# half-pint-turbidimeter_tsl230rd_2_0_1.net
KiCad netlist of a schematic drawn in EAGLE
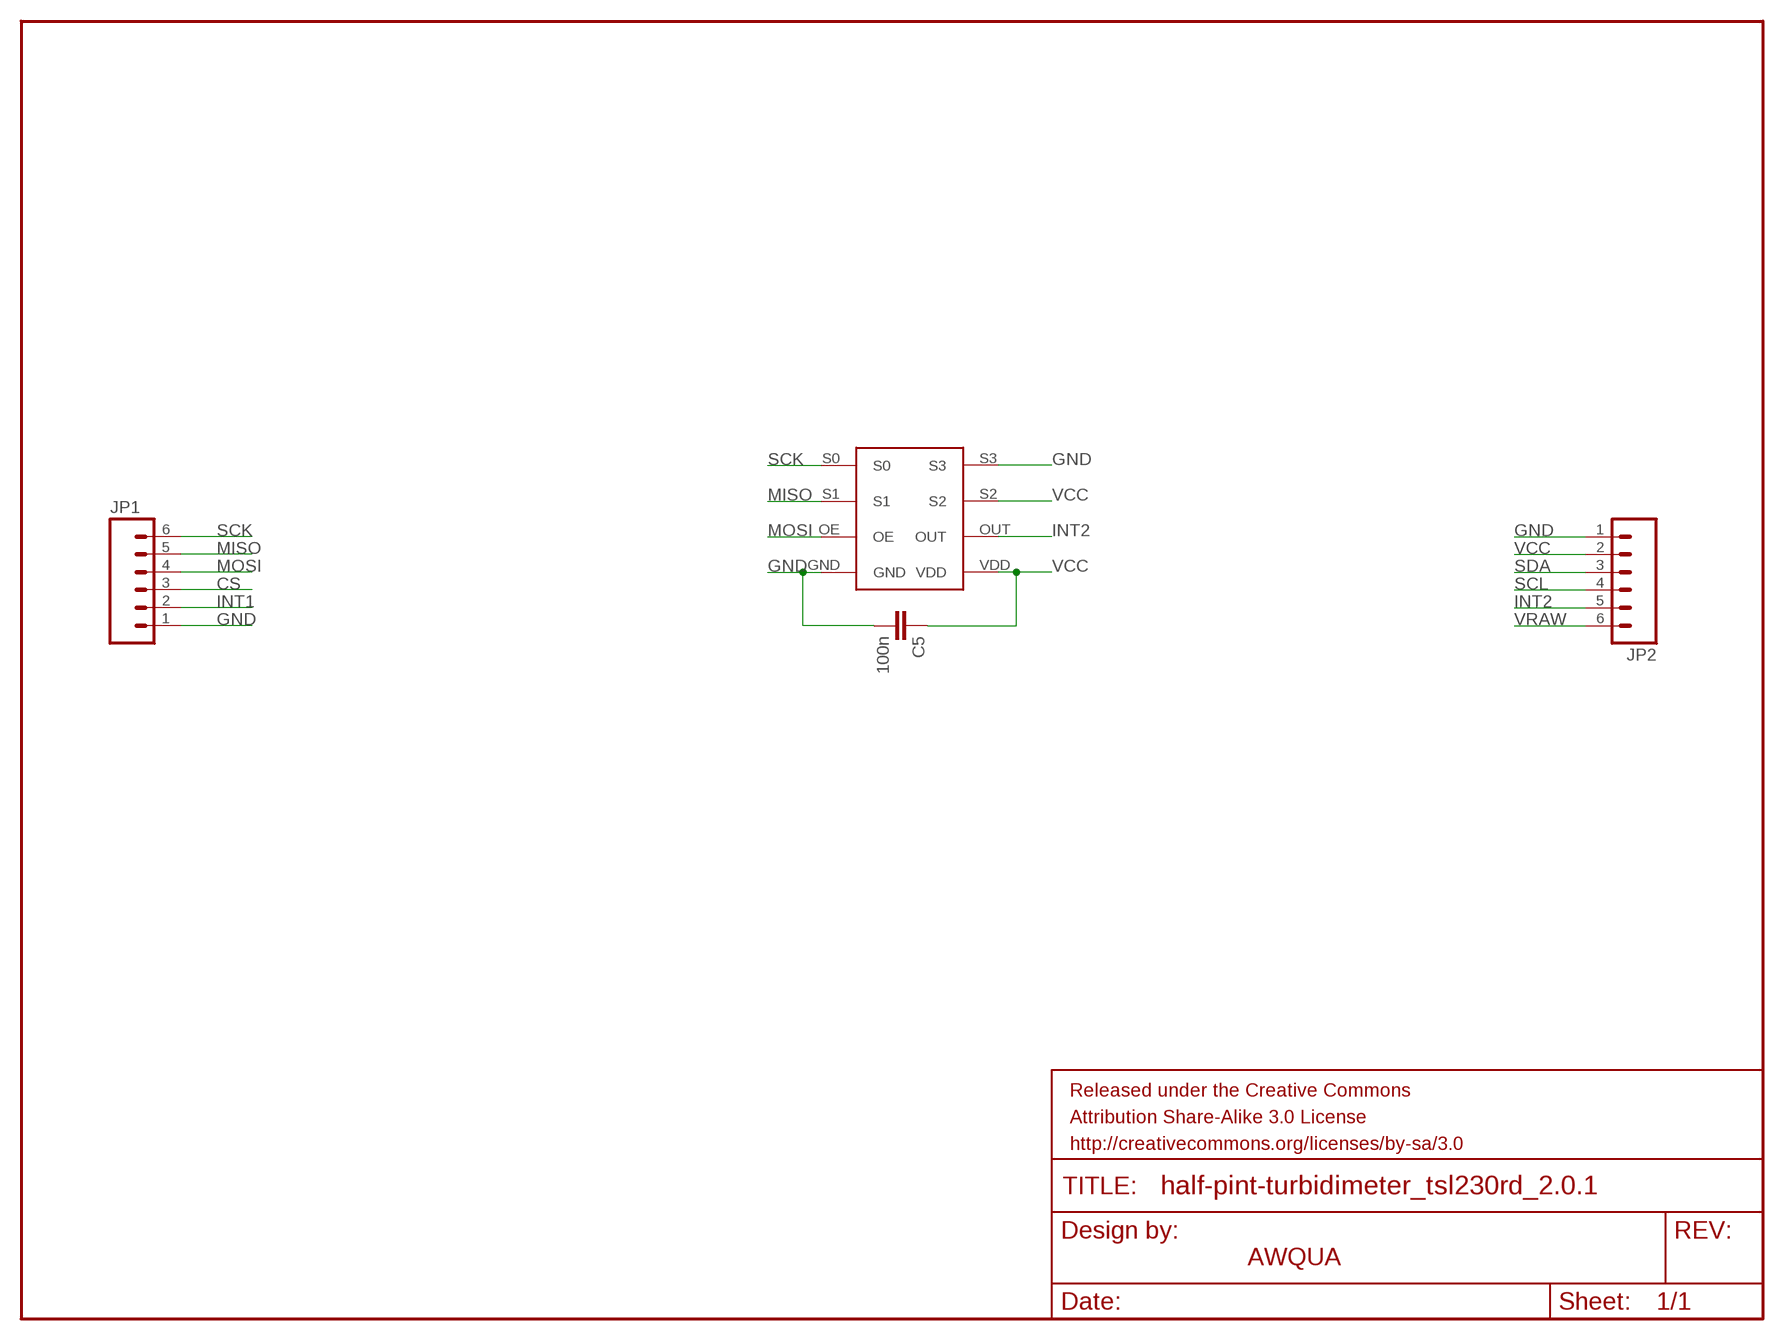
[diagram p0: schematic, sheet 1]

(export (version "E")
  (design (tool "Eeschema 10.0.6"))
  (components
    (comp (ref "C5")
      (value "100n")
      (footprint "eagle-import:0603-CAP")
      (libsource (lib "eagle-import") (part "CAP0603-CAP"))
    )
    (comp (ref "FRAME1")
      (value "FRAME-LETTER")
      (footprint "eagle-import:CREATIVE_COMMONS")
      (libsource (lib "eagle-import") (part "FRAME-LETTER"))
    )
    (comp (ref "JP1")
      (value "M06SIP")
      (footprint "eagle-import:1X06")
      (libsource (lib "eagle-import") (part "M06SIP"))
    )
    (comp (ref "JP2")
      (value "M06SIP")
      (footprint "eagle-import:1X06")
      (libsource (lib "eagle-import") (part "M06SIP"))
    )
    (comp (ref "U$6")
      (value "TSL230RDSMD")
      (footprint "eagle-import:TSL230RD")
      (libsource (lib "eagle-import") (part "TSL230RDSMD"))
    )
  )
  (nets
    (net (code "1") (name "/CS") (class "Default")
      (node (ref "JP1") (pin "3") (pinfunction "3_3") (pintype "passive"))
    )
    (net (code "2") (name "/GND") (class "Default")
      (node (ref "C5") (pin "2") (pinfunction "2_2") (pintype "passive"))
      (node (ref "JP1") (pin "1") (pinfunction "1_1") (pintype "passive"))
      (node (ref "JP2") (pin "1") (pinfunction "1_1") (pintype "passive"))
      (node (ref "U$6") (pin "GND") (pinfunction "GND_GND") (pintype "bidirectional"))
      (node (ref "U$6") (pin "S3") (pinfunction "S3_S3") (pintype "bidirectional"))
    )
    (net (code "3") (name "/INT1") (class "Default")
      (node (ref "JP1") (pin "2") (pinfunction "2_2") (pintype "passive"))
    )
    (net (code "4") (name "/INT2") (class "Default")
      (node (ref "JP2") (pin "5") (pinfunction "5_5") (pintype "passive"))
      (node (ref "U$6") (pin "OUT") (pinfunction "OUT_OUT") (pintype "bidirectional"))
    )
    (net (code "5") (name "/MISO") (class "Default")
      (node (ref "JP1") (pin "5") (pinfunction "5_5") (pintype "passive"))
      (node (ref "U$6") (pin "S1") (pinfunction "S1_S1") (pintype "bidirectional"))
    )
    (net (code "6") (name "/MOSI") (class "Default")
      (node (ref "JP1") (pin "4") (pinfunction "4_4") (pintype "passive"))
      (node (ref "U$6") (pin "OE") (pinfunction "OE_OE") (pintype "bidirectional"))
    )
    (net (code "7") (name "/SCK") (class "Default")
      (node (ref "JP1") (pin "6") (pinfunction "6_6") (pintype "passive"))
      (node (ref "U$6") (pin "S0") (pinfunction "S0_S0") (pintype "bidirectional"))
    )
    (net (code "8") (name "/SCL") (class "Default")
      (node (ref "JP2") (pin "4") (pinfunction "4_4") (pintype "passive"))
    )
    (net (code "9") (name "/SDA") (class "Default")
      (node (ref "JP2") (pin "3") (pinfunction "3_3") (pintype "passive"))
    )
    (net (code "10") (name "/VCC") (class "Default")
      (node (ref "C5") (pin "1") (pinfunction "1_1") (pintype "passive"))
      (node (ref "JP2") (pin "2") (pinfunction "2_2") (pintype "passive"))
      (node (ref "U$6") (pin "S2") (pinfunction "S2_S2") (pintype "bidirectional"))
      (node (ref "U$6") (pin "VDD") (pinfunction "VDD_VDD") (pintype "bidirectional"))
    )
    (net (code "11") (name "/VRAW") (class "Default")
      (node (ref "JP2") (pin "6") (pinfunction "6_6") (pintype "passive"))
    )
  )
)
